# BOC_LCD.net
KiCad netlist of a schematic drawn in Altium Designer
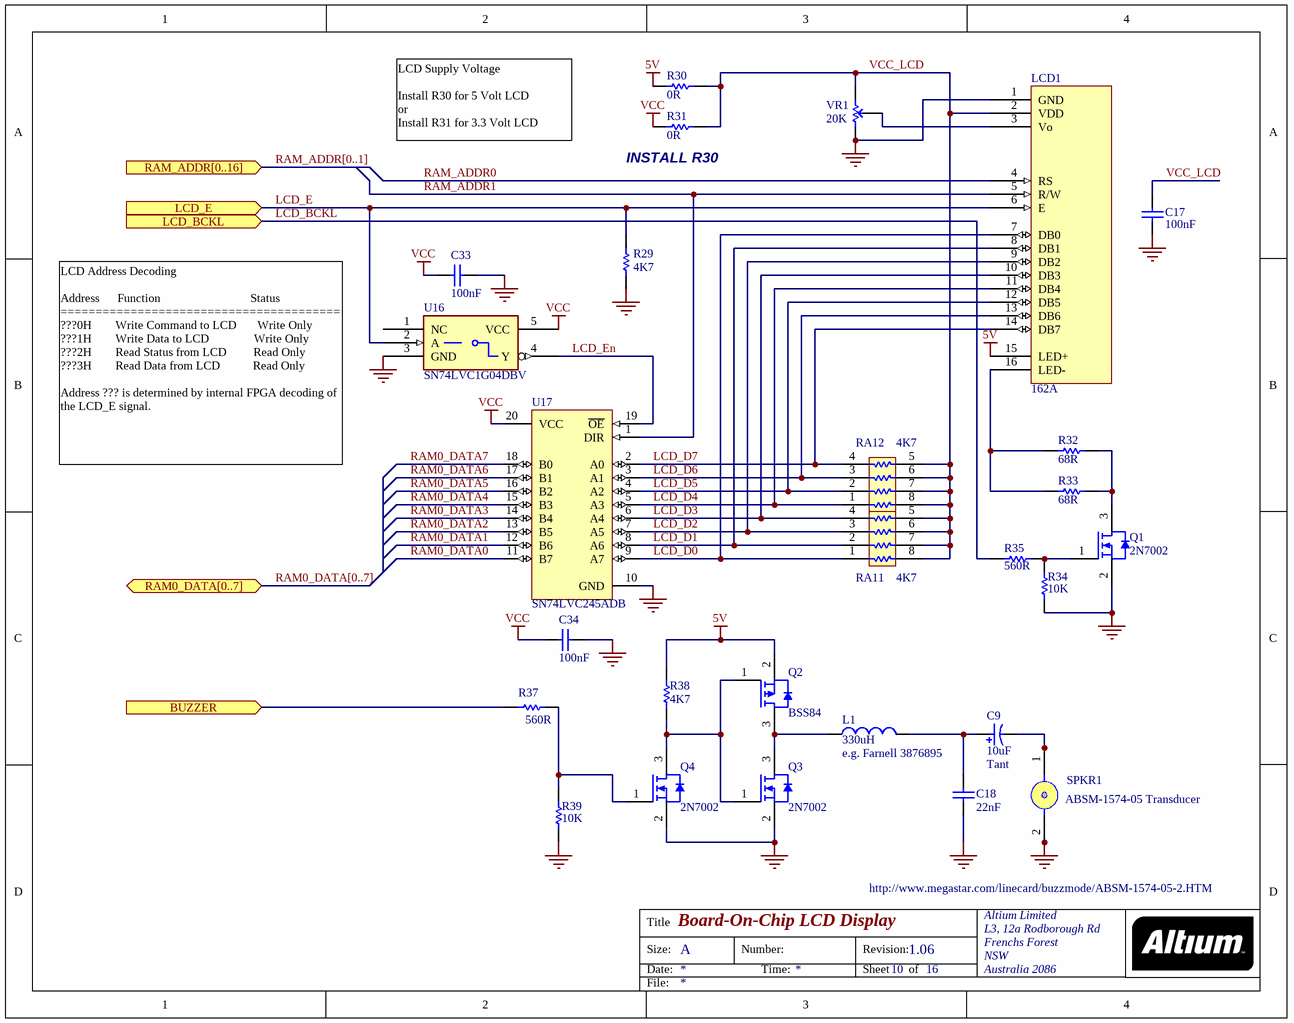
[diagram p0: BOC_LCD.SchDoc]

(export (version "E")
  (design (tool "Eeschema 10.0.6"))
  (components
    (comp (ref "C9")
      (value "10uF")
      (footprint "Altium Nanoboard Project:MCCT-B")
      (description "Polar Capacitor")
      (fields (field (name "CAPACITOR TYPE") "Tant"))
      (libsource (lib "Altium Nanoboard Project") (part "CAP_POLAR"))
    )
    (comp (ref "C17")
      (value "100nF")
      (footprint "Altium Nanoboard Project:CC2012-0805")
      (description "Capacitor")
      (libsource (lib "Altium Nanoboard Project") (part "CAP"))
    )
    (comp (ref "C18")
      (value "22nF")
      (footprint "Altium Nanoboard Project:CC2012-0805")
      (description "Capacitor")
      (libsource (lib "Altium Nanoboard Project") (part "CAP"))
    )
    (comp (ref "C33")
      (value "100nF")
      (footprint "Altium Nanoboard Project:CC2012-0805")
      (description "Capacitor")
      (libsource (lib "Altium Nanoboard Project") (part "CAP"))
    )
    (comp (ref "C34")
      (value "100nF")
      (footprint "Altium Nanoboard Project:CC2012-0805")
      (description "Capacitor")
      (libsource (lib "Altium Nanoboard Project") (part "CAP"))
    )
    (comp (ref "L1")
      (value "330uH")
      (footprint "Altium Nanoboard Project:CC4532-1812")
      (description "Inductor e.g. Farnell 3876895")
      (fields (field (name "PART NO") "e.g. Farnell 3876895"))
      (libsource (lib "Altium Nanoboard Project") (part "INDUCTOR"))
    )
    (comp (ref "LCD1")
      (value "162A")
      (footprint "Altium Nanoboard Project:162A")
      (description "16 char * 2 line LCD character display with b/light")
      (libsource (lib "Altium Nanoboard Project") (part "162A"))
    )
    (comp (ref "Q1")
      (value "2N7002")
      (footprint "Altium Nanoboard Project:SO-G3")
      (description "N Channel Mosfet")
      (libsource (lib "Altium Nanoboard Project") (part "2N7002"))
    )
    (comp (ref "Q2")
      (value "BSS84")
      (footprint "Altium Nanoboard Project:SO-G3")
      (description "P Channel Mosfet")
      (libsource (lib "Altium Nanoboard Project") (part "BSS84"))
    )
    (comp (ref "Q3")
      (value "2N7002")
      (footprint "Altium Nanoboard Project:SO-G3")
      (description "N Channel Mosfet")
      (libsource (lib "Altium Nanoboard Project") (part "2N7002"))
    )
    (comp (ref "Q4")
      (value "2N7002")
      (footprint "Altium Nanoboard Project:SO-G3")
      (description "N Channel Mosfet")
      (libsource (lib "Altium Nanoboard Project") (part "2N7002"))
    )
    (comp (ref "R29")
      (value "4K7")
      (footprint "Altium Nanoboard Project:CC2012-0805")
      (description "Resistor")
      (libsource (lib "Altium Nanoboard Project") (part "RES"))
    )
    (comp (ref "R30")
      (value "0R")
      (footprint "Altium Nanoboard Project:CC2012-0805")
      (description "Resistor")
      (libsource (lib "Altium Nanoboard Project") (part "RES"))
    )
    (comp (ref "R31")
      (value "0R")
      (footprint "Altium Nanoboard Project:CC2012-0805")
      (description "Resistor")
      (libsource (lib "Altium Nanoboard Project") (part "RES"))
    )
    (comp (ref "R32")
      (value "68R")
      (footprint "Altium Nanoboard Project:CC2012-0805")
      (description "Resistor")
      (libsource (lib "Altium Nanoboard Project") (part "RES"))
    )
    (comp (ref "R33")
      (value "68R")
      (footprint "Altium Nanoboard Project:CC2012-0805")
      (description "Resistor")
      (libsource (lib "Altium Nanoboard Project") (part "RES"))
    )
    (comp (ref "R34")
      (value "10K")
      (footprint "Altium Nanoboard Project:CC2012-0805")
      (description "Resistor")
      (libsource (lib "Altium Nanoboard Project") (part "RES"))
    )
    (comp (ref "R35")
      (value "560R")
      (footprint "Altium Nanoboard Project:CC2012-0805")
      (description "Resistor")
      (libsource (lib "Altium Nanoboard Project") (part "RES"))
    )
    (comp (ref "R37")
      (value "560R")
      (footprint "Altium Nanoboard Project:CC2012-0805")
      (description "Resistor")
      (libsource (lib "Altium Nanoboard Project") (part "RES"))
    )
    (comp (ref "R38")
      (value "4K7")
      (footprint "Altium Nanoboard Project:CC2012-0805")
      (description "Resistor")
      (libsource (lib "Altium Nanoboard Project") (part "RES"))
    )
    (comp (ref "R39")
      (value "10K")
      (footprint "Altium Nanoboard Project:CC2012-0805")
      (description "Resistor")
      (libsource (lib "Altium Nanoboard Project") (part "RES"))
    )
    (comp (ref "RA11")
      (value "4K7")
      (footprint "Altium Nanoboard Project:MNR34")
      (description "3216x4 Resistor Array")
      (libsource (lib "Altium Nanoboard Project") (part "MNR34"))
    )
    (comp (ref "RA12")
      (value "4K7")
      (footprint "Altium Nanoboard Project:MNR34")
      (description "3216x4 Resistor Array")
      (libsource (lib "Altium Nanoboard Project") (part "MNR34"))
    )
    (comp (ref "SPKR1")
      (value "ABSM-1574-05 Transducer")
      (footprint "Altium Nanoboard Project:ABSM-1574")
      (description "Megastar Subminiature Transducer")
      (fields (field (name "WEB") "http://www.megastar.com/linecard/buzzmode/ABSM-1574-05-2.HTM"))
      (libsource (lib "Altium Nanoboard Project") (part "ABSM-1574-05 Transducer"))
    )
    (comp (ref "U16")
      (value "SN74LVC1G04DBV")
      (footprint "Altium Nanoboard Project:SO-G5/P.95")
      (fields (field (name "MANUFACTURER") "TI"))
      (libsource (lib "Altium Nanoboard Project") (part "SN74AHC1G04DBVR"))
    )
    (comp (ref "U17")
      (value "SN74LVC245ADB")
      (footprint "Altium Nanoboard Project:SSO-G20/P.65")
      (description "Octal Bus Transceiver with 3-State Outputs")
      (fields (field (name "MANUFACTURER") "Texas Instruments") (field (name "PUBLISHER") "Altium Limited"))
      (libsource (lib "Altium Nanoboard Project") (part "74LVC245A"))
    )
    (comp (ref "VR1")
      (value "20K")
      (footprint "Altium Nanoboard Project:POT4MM-2")
      (description "Potentiometer")
      (libsource (lib "Altium Nanoboard Project") (part "POT_M"))
    )
  )
  (nets
    (net (code "1") (name "/BUZZER") (class "Default")
      (node (ref "R37") (pin "1") (pinfunction "1_1") (pintype "passive"))
    )
    (net (code "2") (name "/LCD_BCKL") (class "Default")
      (node (ref "R35") (pin "1") (pinfunction "1_1") (pintype "passive"))
    )
    (net (code "3") (name "/LCD_D0") (class "Default")
      (node (ref "LCD1") (pin "7") (pinfunction "DB0_7") (pintype "bidirectional"))
      (node (ref "RA11") (pin "1") (pintype "passive"))
      (node (ref "U17") (pin "9") (pinfunction "A7_9") (pintype "bidirectional"))
    )
    (net (code "4") (name "/LCD_D1") (class "Default")
      (node (ref "LCD1") (pin "8") (pinfunction "DB1_8") (pintype "bidirectional"))
      (node (ref "RA11") (pin "2") (pintype "passive"))
      (node (ref "U17") (pin "8") (pinfunction "A6_8") (pintype "bidirectional"))
    )
    (net (code "5") (name "/LCD_D2") (class "Default")
      (node (ref "LCD1") (pin "9") (pinfunction "DB2_9") (pintype "bidirectional"))
      (node (ref "RA11") (pin "3") (pintype "passive"))
      (node (ref "U17") (pin "7") (pinfunction "A5_7") (pintype "bidirectional"))
    )
    (net (code "6") (name "/LCD_D3") (class "Default")
      (node (ref "LCD1") (pin "10") (pinfunction "DB3_10") (pintype "bidirectional"))
      (node (ref "RA11") (pin "4") (pintype "passive"))
      (node (ref "U17") (pin "6") (pinfunction "A4_6") (pintype "bidirectional"))
    )
    (net (code "7") (name "/LCD_D4") (class "Default")
      (node (ref "LCD1") (pin "11") (pinfunction "DB4_11") (pintype "bidirectional"))
      (node (ref "RA12") (pin "1") (pintype "passive"))
      (node (ref "U17") (pin "5") (pinfunction "A3_5") (pintype "bidirectional"))
    )
    (net (code "8") (name "/LCD_D5") (class "Default")
      (node (ref "LCD1") (pin "12") (pinfunction "DB5_12") (pintype "bidirectional"))
      (node (ref "RA12") (pin "2") (pintype "passive"))
      (node (ref "U17") (pin "4") (pinfunction "A2_4") (pintype "bidirectional"))
    )
    (net (code "9") (name "/LCD_D6") (class "Default")
      (node (ref "LCD1") (pin "13") (pinfunction "DB6_13") (pintype "bidirectional"))
      (node (ref "RA12") (pin "3") (pintype "passive"))
      (node (ref "U17") (pin "3") (pinfunction "A1_3") (pintype "bidirectional"))
    )
    (net (code "10") (name "/LCD_D7") (class "Default")
      (node (ref "LCD1") (pin "14") (pinfunction "DB7_14") (pintype "bidirectional"))
      (node (ref "RA12") (pin "4") (pintype "passive"))
      (node (ref "U17") (pin "2") (pinfunction "A0_2") (pintype "bidirectional"))
    )
    (net (code "11") (name "/LCD_E") (class "Default")
      (node (ref "LCD1") (pin "6") (pinfunction "E_6") (pintype "input"))
      (node (ref "R29") (pin "1") (pinfunction "1_1") (pintype "passive"))
      (node (ref "U16") (pin "2") (pinfunction "A_2") (pintype "input"))
    )
    (net (code "12") (name "/LCD_En") (class "Default")
      (node (ref "U16") (pin "4") (pinfunction "Y_4") (pintype "output"))
      (node (ref "U17") (pin "19") (pinfunction "~{OE}_19") (pintype "input"))
    )
    (net (code "13") (name "/RAM0_DATA0") (class "Default")
      (node (ref "U17") (pin "11") (pinfunction "B7_11") (pintype "bidirectional"))
    )
    (net (code "14") (name "/RAM0_DATA1") (class "Default")
      (node (ref "U17") (pin "12") (pinfunction "B6_12") (pintype "bidirectional"))
    )
    (net (code "15") (name "/RAM0_DATA2") (class "Default")
      (node (ref "U17") (pin "13") (pinfunction "B5_13") (pintype "bidirectional"))
    )
    (net (code "16") (name "/RAM0_DATA3") (class "Default")
      (node (ref "U17") (pin "14") (pinfunction "B4_14") (pintype "bidirectional"))
    )
    (net (code "17") (name "/RAM0_DATA4") (class "Default")
      (node (ref "U17") (pin "15") (pinfunction "B3_15") (pintype "bidirectional"))
    )
    (net (code "18") (name "/RAM0_DATA5") (class "Default")
      (node (ref "U17") (pin "16") (pinfunction "B2_16") (pintype "bidirectional"))
    )
    (net (code "19") (name "/RAM0_DATA6") (class "Default")
      (node (ref "U17") (pin "17") (pinfunction "B1_17") (pintype "bidirectional"))
    )
    (net (code "20") (name "/RAM0_DATA7") (class "Default")
      (node (ref "U17") (pin "18") (pinfunction "B0_18") (pintype "bidirectional"))
    )
    (net (code "22") (name "/RAM_ADDR0") (class "Default")
      (node (ref "LCD1") (pin "4") (pinfunction "RS_4") (pintype "input"))
    )
    (net (code "23") (name "/RAM_ADDR1") (class "Default")
      (node (ref "LCD1") (pin "5") (pinfunction "R/W_5") (pintype "input"))
      (node (ref "U17") (pin "1") (pinfunction "DIR_1") (pintype "input"))
    )
    (net (code "25") (name "/VCC_LCD") (class "Default")
      (node (ref "C17") (pin "1") (pinfunction "1_1") (pintype "passive"))
      (node (ref "LCD1") (pin "2") (pinfunction "VDD_2") (pintype "power_in"))
      (node (ref "R30") (pin "2") (pinfunction "2_2") (pintype "passive"))
      (node (ref "R31") (pin "2") (pinfunction "2_2") (pintype "passive"))
      (node (ref "RA11") (pin "5") (pintype "passive"))
      (node (ref "RA11") (pin "6") (pintype "passive"))
      (node (ref "RA11") (pin "7") (pintype "passive"))
      (node (ref "RA11") (pin "8") (pintype "passive"))
      (node (ref "RA12") (pin "5") (pintype "passive"))
      (node (ref "RA12") (pin "6") (pintype "passive"))
      (node (ref "RA12") (pin "7") (pintype "passive"))
      (node (ref "RA12") (pin "8") (pintype "passive"))
      (node (ref "VR1") (pin "CW") (pinfunction "+_CW") (pintype "passive"))
    )
    (net (code "26") (name "5V") (class "Default")
      (node (ref "LCD1") (pin "15") (pinfunction "LED+_15") (pintype "power_in"))
      (node (ref "Q2") (pin "2") (pintype "passive"))
      (node (ref "R30") (pin "1") (pinfunction "1_1") (pintype "passive"))
      (node (ref "R38") (pin "1") (pinfunction "1_1") (pintype "passive"))
    )
    (net (code "27") (name "GND") (class "Default")
      (node (ref "C17") (pin "2") (pinfunction "2_2") (pintype "passive"))
      (node (ref "C18") (pin "2") (pinfunction "2_2") (pintype "passive"))
      (node (ref "C33") (pin "2") (pinfunction "2_2") (pintype "passive"))
      (node (ref "C34") (pin "2") (pinfunction "2_2") (pintype "passive"))
      (node (ref "LCD1") (pin "1") (pinfunction "GND_1") (pintype "power_in"))
      (node (ref "Q1") (pin "2") (pintype "passive"))
      (node (ref "Q3") (pin "2") (pintype "passive"))
      (node (ref "Q4") (pin "2") (pintype "passive"))
      (node (ref "R29") (pin "2") (pinfunction "2_2") (pintype "passive"))
      (node (ref "R34") (pin "1") (pinfunction "1_1") (pintype "passive"))
      (node (ref "R39") (pin "2") (pinfunction "2_2") (pintype "passive"))
      (node (ref "SPKR1") (pin "2") (pinfunction "2_2") (pintype "passive"))
      (node (ref "SPKR1") (pin "2A") (pinfunction "2A_2A") (pintype "passive"))
      (node (ref "U16") (pin "3") (pinfunction "GND_3") (pintype "power_in"))
      (node (ref "U17") (pin "10") (pinfunction "GND_10") (pintype "power_in"))
      (node (ref "VR1") (pin "CCW") (pinfunction "-_CCW") (pintype "passive"))
    )
    (net (code "28") (name "Net-(C9-Pad2)") (class "Default")
      (node (ref "C9") (pin "2") (pinfunction "2_2") (pintype "passive"))
      (node (ref "SPKR1") (pin "1") (pinfunction "1_1") (pintype "passive"))
      (node (ref "SPKR1") (pin "1A") (pinfunction "1A_1A") (pintype "passive"))
    )
    (net (code "29") (name "Net-(C18-Pad1)") (class "Default")
      (node (ref "C18") (pin "1") (pinfunction "1_1") (pintype "passive"))
      (node (ref "C9") (pin "1") (pinfunction "1_1") (pintype "passive"))
      (node (ref "L1") (pin "2") (pinfunction "2_2") (pintype "passive"))
    )
    (net (code "30") (name "Net-(L1-Pad1)") (class "Default")
      (node (ref "L1") (pin "1") (pinfunction "1_1") (pintype "passive"))
      (node (ref "Q2") (pin "3") (pintype "passive"))
      (node (ref "Q3") (pin "3") (pintype "passive"))
    )
    (net (code "31") (name "Net-(LCD1-LED-)") (class "Default")
      (node (ref "LCD1") (pin "16") (pinfunction "LED-_16") (pintype "power_in"))
      (node (ref "R32") (pin "1") (pinfunction "1_1") (pintype "passive"))
      (node (ref "R33") (pin "1") (pinfunction "1_1") (pintype "passive"))
    )
    (net (code "32") (name "Net-(LCD1-Vo)") (class "Default")
      (node (ref "LCD1") (pin "3") (pinfunction "Vo_3") (pintype "tri_state"))
      (node (ref "VR1") (pin "W") (pintype "passive"))
    )
    (net (code "33") (name "Net-(Q1-Pad1)") (class "Default")
      (node (ref "Q1") (pin "1") (pintype "passive"))
      (node (ref "R34") (pin "2") (pinfunction "2_2") (pintype "passive"))
      (node (ref "R35") (pin "2") (pinfunction "2_2") (pintype "passive"))
    )
    (net (code "34") (name "Net-(Q1-Pad3)") (class "Default")
      (node (ref "Q1") (pin "3") (pintype "passive"))
      (node (ref "R32") (pin "2") (pinfunction "2_2") (pintype "passive"))
      (node (ref "R33") (pin "2") (pinfunction "2_2") (pintype "passive"))
    )
    (net (code "35") (name "Net-(Q2-Pad1)") (class "Default")
      (node (ref "Q2") (pin "1") (pintype "passive"))
      (node (ref "Q3") (pin "1") (pintype "passive"))
      (node (ref "Q4") (pin "3") (pintype "passive"))
      (node (ref "R38") (pin "2") (pinfunction "2_2") (pintype "passive"))
    )
    (net (code "36") (name "Net-(Q4-Pad1)") (class "Default")
      (node (ref "Q4") (pin "1") (pintype "passive"))
      (node (ref "R37") (pin "2") (pinfunction "2_2") (pintype "passive"))
      (node (ref "R39") (pin "1") (pinfunction "1_1") (pintype "passive"))
    )
    (net (code "37") (name "VCC") (class "Default")
      (node (ref "C33") (pin "1") (pinfunction "1_1") (pintype "passive"))
      (node (ref "C34") (pin "1") (pinfunction "1_1") (pintype "passive"))
      (node (ref "R31") (pin "1") (pinfunction "1_1") (pintype "passive"))
      (node (ref "U16") (pin "5") (pinfunction "VCC_5") (pintype "power_in"))
      (node (ref "U17") (pin "20") (pinfunction "VCC_20") (pintype "power_in"))
    )
    (net (code "38") (name "unconnected-(U16-NC-Pad1)") (class "Default")
      (node (ref "U16") (pin "1") (pinfunction "NC_1") (pintype "passive"))
    )
  )
)
